# J-Link-OB.net
KiCad netlist of a schematic drawn in Altium Designer
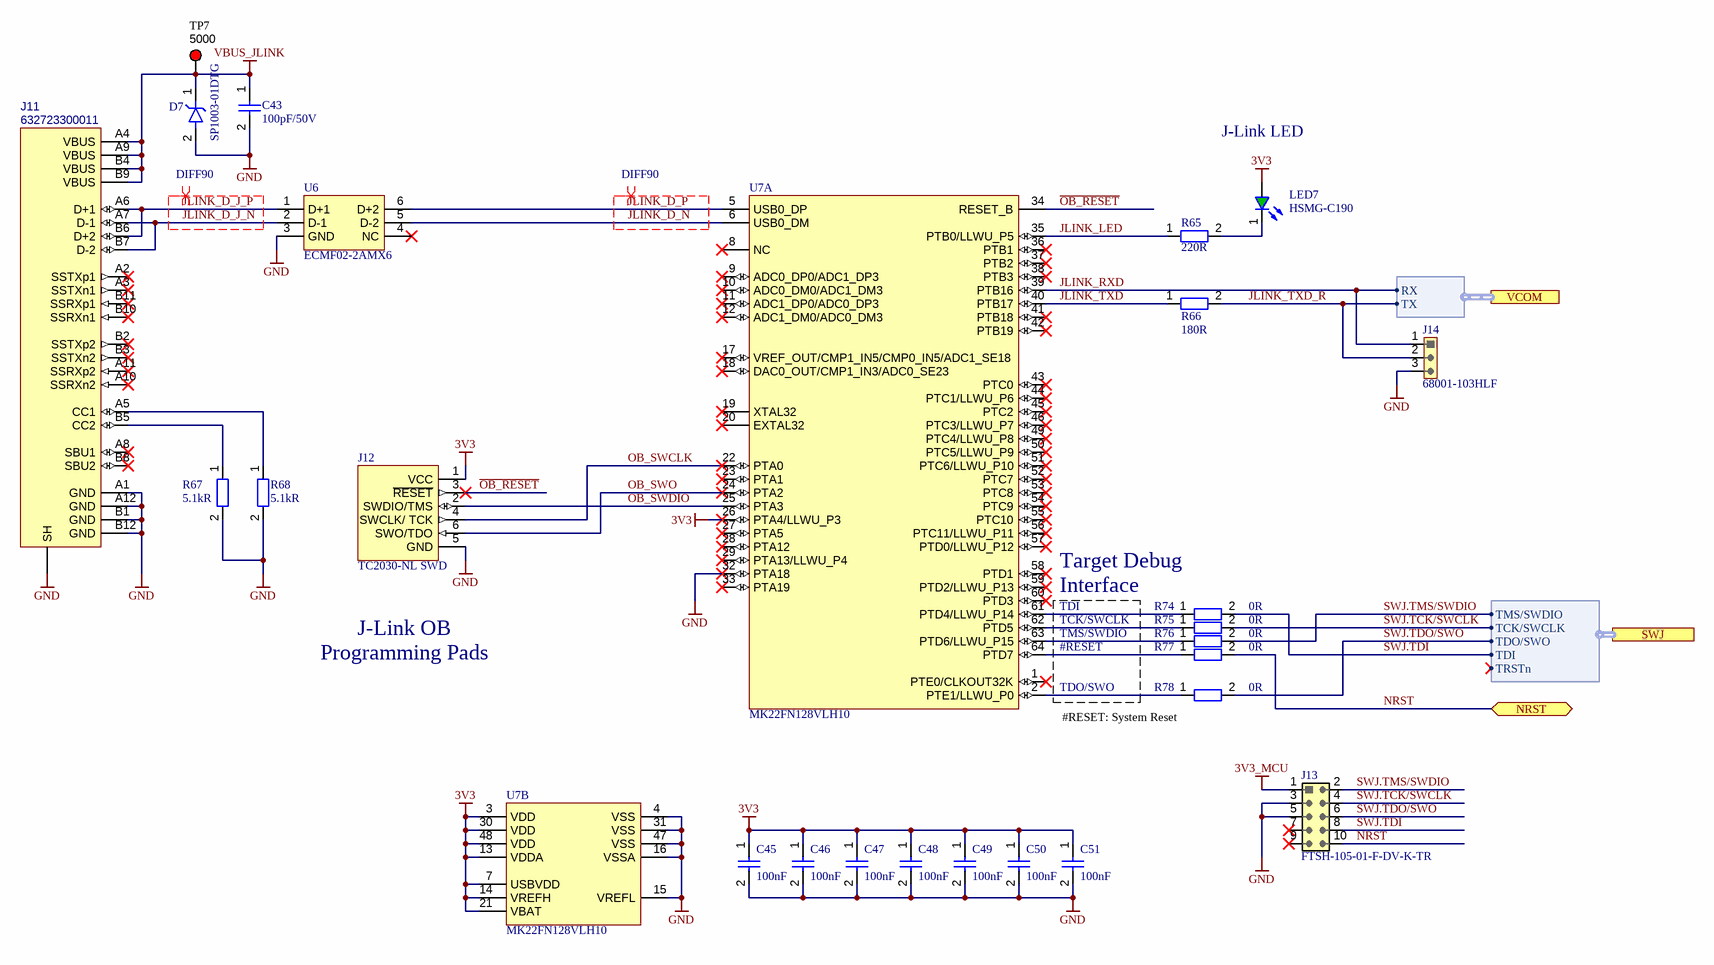
[diagram p0: J-Link-OB.SchDoc]

(export (version "E")
  (design (tool "Eeschema 10.0.6"))
  (components
    (comp (ref "C43")
      (value "100pF/50V")
      (footprint "CAPC1005X50N")
      (description "Cap MLCC, 100pF, 50V, C0G, 5%, 0402")
      (fields (field (name "TOLERANCE") "5%"))
      (libsource (lib "ZHAW on Altium 365") (part "CAP-NP-2"))
    )
    (comp (ref "C45")
      (value "100nF")
      (footprint "CAPC1005X50N")
      (description "Cap MLCC, 100nF, 16V, X7R, 5%,  0402")
      (fields (field (name "TOLERANCE") "5%") (field (name "Comment") "100nF/16V"))
      (libsource (lib "ZHAW on Altium 365") (part "CAP-NP-2"))
    )
    (comp (ref "C46")
      (value "100nF")
      (footprint "CAPC1005X50N")
      (description "Cap MLCC, 100nF, 16V, X7R, 5%,  0402")
      (fields (field (name "TOLERANCE") "5%") (field (name "Comment") "100nF/16V"))
      (libsource (lib "ZHAW on Altium 365") (part "CAP-NP-2"))
    )
    (comp (ref "C47")
      (value "100nF")
      (footprint "CAPC1005X50N")
      (description "Cap MLCC, 100nF, 16V, X7R, 5%,  0402")
      (fields (field (name "TOLERANCE") "5%") (field (name "Comment") "100nF/16V"))
      (libsource (lib "ZHAW on Altium 365") (part "CAP-NP-2"))
    )
    (comp (ref "C48")
      (value "100nF")
      (footprint "CAPC1005X50N")
      (description "Cap MLCC, 100nF, 16V, X7R, 5%,  0402")
      (fields (field (name "TOLERANCE") "5%") (field (name "Comment") "100nF/16V"))
      (libsource (lib "ZHAW on Altium 365") (part "CAP-NP-2"))
    )
    (comp (ref "C49")
      (value "100nF")
      (footprint "CAPC1005X50N")
      (description "Cap MLCC, 100nF, 16V, X7R, 5%,  0402")
      (fields (field (name "TOLERANCE") "5%") (field (name "Comment") "100nF/16V"))
      (libsource (lib "ZHAW on Altium 365") (part "CAP-NP-2"))
    )
    (comp (ref "C50")
      (value "100nF")
      (footprint "CAPC1005X50N")
      (description "Cap MLCC, 100nF, 16V, X7R, 5%,  0402")
      (fields (field (name "TOLERANCE") "5%") (field (name "Comment") "100nF/16V"))
      (libsource (lib "ZHAW on Altium 365") (part "CAP-NP-2"))
    )
    (comp (ref "C51")
      (value "100nF")
      (footprint "CAPC1005X50N")
      (description "Cap MLCC, 100nF, 16V, X7R, 5%,  0402")
      (fields (field (name "TOLERANCE") "5%") (field (name "Comment") "100nF/16V"))
      (libsource (lib "ZHAW on Altium 365") (part "CAP-NP-2"))
    )
    (comp (ref "D7")
      (value "SP1003-01DTG")
      (footprint "SOD14060X55N")
      (description "TVS Diode, unidirectional, 5V, 7A, SOD723")
      (libsource (lib "ZHAW on Altium 365") (part "D-TVS-KA-2"))
    )
    (comp (ref "J11")
      (value "632723300011")
      (footprint "WE_632723300011")
      (description "USB-C, 24 Pin, Pitch 500um, 20V, Horizontal, SMD/THT, L11.2B8.74H2.96")
      (fields (field (name "MANUFACTURER") "Wurth Elektronik"))
      (libsource (lib "ZHAW on Altium 365") (part "CN-USB-C-24"))
    )
    (comp (ref "J12")
      (value "TC2030-NL SWD")
      (footprint "TC2030-NL")
      (description "Land Pattern, Cortex Tag-Connect, 6 Pin, Pitch 1.27mm, no legs")
      (fields (field (name "MATING PART") "Cortex Tag-Connect Debugger"))
      (libsource (lib "ZHAW on Altium 365") (part "CN-TC2030-6"))
    )
    (comp (ref "J13")
      (value "FTSH-105-01-F-DV-K-TR")
      (footprint "FP-FTSH-105-01-F-DV-K-TR-MFG")
      (description "Box Header, FTSH-105, 2x5 Pin, Pitch 1.27mm, 3.4A, Vertical, SMD, L6.3B6.86H6")
      (fields (field (name "MANUFACTURER") "Samtec Inc."))
      (libsource (lib "ZHAW on Altium 365") (part "CN-BOXHDR-2x05-M-10"))
    )
    (comp (ref "J14")
      (value "68001-103HLF")
      (footprint "HD254_1x3_MV")
      (description "Header, 1x3 Pin, Pitch 2.54mm, Male, Vertical, THT")
      (fields (field (name "MANUFACTURER") "FCI"))
      (libsource (lib "ZHAW on Altium 365") (part "HDR-1x03-M-3"))
    )
    (comp (ref "LED7")
      (value "HSMG-C190")
      (footprint "LEDSC160X80X80-2Lgn")
      (description "LED, Green, 20mA, 2.2V, 0603")
      (libsource (lib "ZHAW on Altium 365") (part "LED-GN-KA-2"))
    )
    (comp (ref "R65")
      (value "220R")
      (footprint "RESC1608X45N")
      (description "Res, 220R, 1%, 0.1W, 0603")
      (fields (field (name "TOLERANCE") "1%") (field (name "POWER") "100mW"))
      (libsource (lib "ZHAW on Altium 365") (part "RES-2"))
    )
    (comp (ref "R66")
      (value "180R")
      (footprint "RESC1608X45N")
      (description "Res, 180R, 1%, 100mW, 0603")
      (fields (field (name "POWER") "100mW") (field (name "TOLERANCE") "1%"))
      (libsource (lib "ZHAW on Altium 365") (part "RES-2"))
    )
    (comp (ref "R67")
      (value "5.1kR")
      (footprint "RESC1005X35N")
      (description "Res, 5.1kR, 1%, 0.063W, 0402")
      (fields (field (name "TOLERANCE") "1%") (field (name "POWER") "63mW"))
      (libsource (lib "") (part "RES-2_1"))
    )
    (comp (ref "R68")
      (value "5.1kR")
      (footprint "RESC1005X35N")
      (description "Res, 5.1kR, 1%, 0.063W, 0402")
      (fields (field (name "TOLERANCE") "1%") (field (name "POWER") "63mW"))
      (libsource (lib "") (part "RES-2_1"))
    )
    (comp (ref "R74")
      (value "0R")
      (footprint "RESC1005X35N")
      (description "Res, 0R, 1%, 0.063W, 0402")
      (fields (field (name "POWER") "63mW") (field (name "TOLERANCE") "1%"))
      (libsource (lib "ZHAW on Altium 365") (part "RES-2"))
    )
    (comp (ref "R75")
      (value "0R")
      (footprint "RESC1005X35N")
      (description "Res, 0R, 1%, 0.063W, 0402")
      (fields (field (name "POWER") "63mW") (field (name "TOLERANCE") "1%"))
      (libsource (lib "ZHAW on Altium 365") (part "RES-2"))
    )
    (comp (ref "R76")
      (value "0R")
      (footprint "RESC1005X35N")
      (description "Res, 0R, 1%, 0.063W, 0402")
      (fields (field (name "POWER") "63mW") (field (name "TOLERANCE") "1%"))
      (libsource (lib "ZHAW on Altium 365") (part "RES-2"))
    )
    (comp (ref "R77")
      (value "0R")
      (footprint "RESC1005X35N")
      (description "Res, 0R, 1%, 0.063W, 0402")
      (fields (field (name "POWER") "63mW") (field (name "TOLERANCE") "1%"))
      (libsource (lib "ZHAW on Altium 365") (part "RES-2"))
    )
    (comp (ref "R78")
      (value "0R")
      (footprint "RESC1005X35N")
      (description "Res, 0R, 1%, 0.063W, 0402")
      (fields (field (name "POWER") "63mW") (field (name "TOLERANCE") "1%"))
      (libsource (lib "ZHAW on Altium 365") (part "RES-2"))
    )
    (comp (ref "TP7")
      (value "5000")
      (footprint "KSTN-5000")
      (description "Test Point, Red, D2.5H4.6, THT, closed ring D1.25")
      (libsource (lib "ZHAW on Altium 365") (part "TP-RD"))
    )
    (comp (ref "U6")
      (value "ECMF02-2AMX6")
      (footprint "QFN50P150X170X50-6N")
      (libsource (lib "ZHAW on Altium 365") (part "EMCMISC-ECMF02-2-6"))
    )
    (comp (ref "U7")
      (value "MK22FN128VLH10")
      (footprint "QFP50P1200X1200X160-64L")
      (description "Microcontroller, ARM Cortex-M4, 32MHz, Flash 128kB, RAM 24kB, QFN-64")
      (libsource (lib "ZHAW on Altium 365") (part "PROCESSOR-MK22FN128VLH10-64"))
    )
  )
  (nets
    (net (code "4") (name "/JLINK_D_J_N") (class "Default")
      (node (ref "J11") (pin "A7") (pinfunction "D-1_A7") (pintype "bidirectional"))
      (node (ref "J11") (pin "B7") (pinfunction "D-2_B7") (pintype "bidirectional"))
      (node (ref "U6") (pin "2") (pinfunction "D-1_2") (pintype "passive"))
    )
    (net (code "5") (name "/JLINK_D_J_P") (class "Default")
      (node (ref "J11") (pin "A6") (pinfunction "D+1_A6") (pintype "bidirectional"))
      (node (ref "J11") (pin "B6") (pinfunction "D+2_B6") (pintype "bidirectional"))
      (node (ref "U6") (pin "1") (pinfunction "D+1_1") (pintype "passive"))
    )
    (net (code "6") (name "/JLINK_D_N") (class "Default")
      (node (ref "U6") (pin "5") (pinfunction "D-2_5") (pintype "passive"))
      (node (ref "U7") (pin "6") (pinfunction "USB0_DM_6") (pintype "passive"))
    )
    (net (code "7") (name "/JLINK_D_P") (class "Default")
      (node (ref "U6") (pin "6") (pinfunction "D+2_6") (pintype "passive"))
      (node (ref "U7") (pin "5") (pinfunction "USB0_DP_5") (pintype "passive"))
    )
    (net (code "8") (name "/JLINK_LED") (class "Default")
      (node (ref "R65") (pin "1") (pinfunction "1_1") (pintype "passive"))
      (node (ref "U7") (pin "35") (pinfunction "PTB0/LLWU_P5_35") (pintype "bidirectional"))
    )
    (net (code "9") (name "/JLINK_RXD") (class "Default")
      (node (ref "J14") (pin "1") (pinfunction "1_1") (pintype "passive"))
      (node (ref "U7") (pin "39") (pinfunction "PTB16_39") (pintype "bidirectional"))
    )
    (net (code "10") (name "/JLINK_TXD") (class "Default")
      (node (ref "R66") (pin "1") (pinfunction "1_1") (pintype "passive"))
      (node (ref "U7") (pin "40") (pinfunction "PTB17_40") (pintype "bidirectional"))
    )
    (net (code "11") (name "/JLINK_TXD_R") (class "Default")
      (node (ref "J14") (pin "2") (pinfunction "2_2") (pintype "passive"))
      (node (ref "R66") (pin "2") (pinfunction "2_2") (pintype "passive"))
    )
    (net (code "12") (name "/NRST") (class "Default")
      (node (ref "J13") (pin "10") (pinfunction "10_10") (pintype "passive"))
      (node (ref "R77") (pin "2") (pinfunction "2_2") (pintype "passive"))
    )
    (net (code "13") (name "/OB_SWCLK") (class "Default")
      (node (ref "J12") (pin "4") (pinfunction "SWCLK/_TCK_4") (pintype "output"))
      (node (ref "U7") (pin "22") (pinfunction "PTA0_22") (pintype "bidirectional"))
    )
    (net (code "14") (name "/OB_SWDIO") (class "Default")
      (node (ref "J12") (pin "2") (pinfunction "SWDIO/TMS_2") (pintype "bidirectional"))
      (node (ref "U7") (pin "25") (pinfunction "PTA3_25") (pintype "bidirectional"))
    )
    (net (code "15") (name "/OB_SWO") (class "Default")
      (node (ref "J12") (pin "6") (pinfunction "SWO/TDO_6") (pintype "input"))
      (node (ref "U7") (pin "24") (pinfunction "PTA2_24") (pintype "bidirectional"))
    )
    (net (code "16") (name "/SWJ.TCK{slash}SWCLK") (class "Default")
      (node (ref "J13") (pin "4") (pinfunction "4_4") (pintype "passive"))
      (node (ref "R75") (pin "2") (pinfunction "2_2") (pintype "passive"))
    )
    (net (code "17") (name "/SWJ.TDI") (class "Default")
      (node (ref "J13") (pin "8") (pinfunction "8_8") (pintype "passive"))
      (node (ref "R74") (pin "2") (pinfunction "2_2") (pintype "passive"))
    )
    (net (code "18") (name "/SWJ.TDO{slash}SWO") (class "Default")
      (node (ref "J13") (pin "6") (pinfunction "6_6") (pintype "passive"))
      (node (ref "R78") (pin "2") (pinfunction "2_2") (pintype "passive"))
    )
    (net (code "19") (name "/SWJ.TMS{slash}SWDIO") (class "Default")
      (node (ref "J13") (pin "2") (pinfunction "2_2") (pintype "passive"))
      (node (ref "R76") (pin "2") (pinfunction "2_2") (pintype "passive"))
    )
    (net (code "22") (name "/~{OB_RESET}") (class "Default")
      (node (ref "J12") (pin "3") (pinfunction "~{RESET}_3") (pintype "output"))
      (node (ref "U7") (pin "34") (pinfunction "RESET_B_34") (pintype "passive"))
    )
    (net (code "23") (name "3V3") (class "Default")
      (node (ref "C45") (pin "1") (pinfunction "1_1") (pintype "passive"))
      (node (ref "C46") (pin "1") (pinfunction "1_1") (pintype "passive"))
      (node (ref "C47") (pin "1") (pinfunction "1_1") (pintype "passive"))
      (node (ref "C48") (pin "1") (pinfunction "1_1") (pintype "passive"))
      (node (ref "C49") (pin "1") (pinfunction "1_1") (pintype "passive"))
      (node (ref "C50") (pin "1") (pinfunction "1_1") (pintype "passive"))
      (node (ref "C51") (pin "1") (pinfunction "1_1") (pintype "passive"))
      (node (ref "J12") (pin "1") (pinfunction "VCC_1") (pintype "passive"))
      (node (ref "LED7") (pin "2") (pinfunction "A_2") (pintype "passive"))
      (node (ref "U7") (pin "13") (pinfunction "VDDA_13") (pintype "power_in"))
      (node (ref "U7") (pin "14") (pinfunction "VREFH_14") (pintype "power_in"))
      (node (ref "U7") (pin "21") (pinfunction "VBAT_21") (pintype "power_in"))
      (node (ref "U7") (pin "26") (pinfunction "PTA4/LLWU_P3_26") (pintype "bidirectional"))
      (node (ref "U7") (pin "3") (pinfunction "VDD_3") (pintype "power_in"))
      (node (ref "U7") (pin "30") (pinfunction "VDD_30") (pintype "power_in"))
      (node (ref "U7") (pin "48") (pinfunction "VDD_48") (pintype "power_in"))
      (node (ref "U7") (pin "7") (pinfunction "USBVDD_7") (pintype "power_in"))
    )
    (net (code "24") (name "3V3_MCU") (class "Default")
      (node (ref "J13") (pin "1") (pinfunction "1_1") (pintype "passive"))
    )
    (net (code "25") (name "GND") (class "Default")
      (node (ref "C43") (pin "2") (pinfunction "2_2") (pintype "passive"))
      (node (ref "C45") (pin "2") (pinfunction "2_2") (pintype "passive"))
      (node (ref "C46") (pin "2") (pinfunction "2_2") (pintype "passive"))
      (node (ref "C47") (pin "2") (pinfunction "2_2") (pintype "passive"))
      (node (ref "C48") (pin "2") (pinfunction "2_2") (pintype "passive"))
      (node (ref "C49") (pin "2") (pinfunction "2_2") (pintype "passive"))
      (node (ref "C50") (pin "2") (pinfunction "2_2") (pintype "passive"))
      (node (ref "C51") (pin "2") (pinfunction "2_2") (pintype "passive"))
      (node (ref "D7") (pin "2") (pinfunction "A_2") (pintype "passive"))
      (node (ref "J11") (pin "A1") (pinfunction "GND_A1") (pintype "power_in"))
      (node (ref "J11") (pin "A12") (pinfunction "GND_A12") (pintype "power_in"))
      (node (ref "J11") (pin "B1") (pinfunction "GND_B1") (pintype "power_in"))
      (node (ref "J11") (pin "B12") (pinfunction "GND_B12") (pintype "power_in"))
      (node (ref "J11") (pin "SH") (pinfunction "SH_SH") (pintype "passive"))
      (node (ref "J12") (pin "5") (pinfunction "GND_5") (pintype "passive"))
      (node (ref "J13") (pin "3") (pinfunction "3_3") (pintype "passive"))
      (node (ref "J13") (pin "5") (pinfunction "5_5") (pintype "passive"))
      (node (ref "J14") (pin "3") (pinfunction "3_3") (pintype "passive"))
      (node (ref "R67") (pin "2") (pinfunction "2_2") (pintype "passive"))
      (node (ref "R68") (pin "2") (pinfunction "2_2") (pintype "passive"))
      (node (ref "U6") (pin "3") (pinfunction "GND_3") (pintype "power_in"))
      (node (ref "U7") (pin "15") (pinfunction "VREFL_15") (pintype "power_in"))
      (node (ref "U7") (pin "16") (pinfunction "VSSA_16") (pintype "power_in"))
      (node (ref "U7") (pin "31") (pinfunction "VSS_31") (pintype "power_in"))
      (node (ref "U7") (pin "32") (pinfunction "PTA18_32") (pintype "bidirectional"))
      (node (ref "U7") (pin "4") (pinfunction "VSS_4") (pintype "power_in"))
      (node (ref "U7") (pin "47") (pinfunction "VSS_47") (pintype "power_in"))
    )
    (net (code "26") (name "Net-(J11-CC1)") (class "Default")
      (node (ref "J11") (pin "A5") (pinfunction "CC1_A5") (pintype "bidirectional"))
      (node (ref "R68") (pin "1") (pinfunction "1_1") (pintype "passive"))
    )
    (net (code "27") (name "Net-(J11-CC2)") (class "Default")
      (node (ref "J11") (pin "B5") (pinfunction "CC2_B5") (pintype "bidirectional"))
      (node (ref "R67") (pin "1") (pinfunction "1_1") (pintype "passive"))
    )
    (net (code "28") (name "Net-(LED7-K)") (class "Default")
      (node (ref "LED7") (pin "1") (pinfunction "K_1") (pintype "passive"))
      (node (ref "R65") (pin "2") (pinfunction "2_2") (pintype "passive"))
    )
    (net (code "29") (name "Net-(U7A-PTD4{slash}LLWU_P14)") (class "Default")
      (node (ref "R74") (pin "1") (pinfunction "1_1") (pintype "passive"))
      (node (ref "U7") (pin "61") (pinfunction "PTD4/LLWU_P14_61") (pintype "bidirectional"))
    )
    (net (code "30") (name "Net-(U7A-PTD5)") (class "Default")
      (node (ref "R75") (pin "1") (pinfunction "1_1") (pintype "passive"))
      (node (ref "U7") (pin "62") (pinfunction "PTD5_62") (pintype "bidirectional"))
    )
    (net (code "31") (name "Net-(U7A-PTD6{slash}LLWU_P15)") (class "Default")
      (node (ref "R76") (pin "1") (pinfunction "1_1") (pintype "passive"))
      (node (ref "U7") (pin "63") (pinfunction "PTD6/LLWU_P15_63") (pintype "bidirectional"))
    )
    (net (code "32") (name "Net-(U7A-PTD7)") (class "Default")
      (node (ref "R77") (pin "1") (pinfunction "1_1") (pintype "passive"))
      (node (ref "U7") (pin "64") (pinfunction "PTD7_64") (pintype "bidirectional"))
    )
    (net (code "33") (name "Net-(U7A-PTE1{slash}LLWU_P0)") (class "Default")
      (node (ref "R78") (pin "1") (pinfunction "1_1") (pintype "passive"))
      (node (ref "U7") (pin "2") (pinfunction "PTE1/LLWU_P0_2") (pintype "bidirectional"))
    )
    (net (code "34") (name "VBUS_JLINK") (class "Default")
      (node (ref "C43") (pin "1") (pinfunction "1_1") (pintype "passive"))
      (node (ref "D7") (pin "1") (pinfunction "A_1") (pintype "passive"))
      (node (ref "J11") (pin "A4") (pinfunction "VBUS_A4") (pintype "power_in"))
      (node (ref "J11") (pin "A9") (pinfunction "VBUS_A9") (pintype "power_in"))
      (node (ref "J11") (pin "B4") (pinfunction "VBUS_B4") (pintype "power_in"))
      (node (ref "J11") (pin "B9") (pinfunction "VBUS_B9") (pintype "power_in"))
      (node (ref "TP7") (pin "1") (pinfunction "1_1") (pintype "passive"))
    )
    (net (code "35") (name "unconnected-(J11-SBU1-PadA8)") (class "Default")
      (node (ref "J11") (pin "A8") (pinfunction "SBU1_A8") (pintype "bidirectional+no_connect"))
    )
    (net (code "36") (name "unconnected-(J11-SBU2-PadB8)") (class "Default")
      (node (ref "J11") (pin "B8") (pinfunction "SBU2_B8") (pintype "bidirectional+no_connect"))
    )
    (net (code "37") (name "unconnected-(J11-SSRXn1-PadB10)") (class "Default")
      (node (ref "J11") (pin "B10") (pinfunction "SSRXn1_B10") (pintype "input+no_connect"))
    )
    (net (code "38") (name "unconnected-(J11-SSRXn2-PadA10)") (class "Default")
      (node (ref "J11") (pin "A10") (pinfunction "SSRXn2_A10") (pintype "input+no_connect"))
    )
    (net (code "39") (name "unconnected-(J11-SSRXp1-PadB11)") (class "Default")
      (node (ref "J11") (pin "B11") (pinfunction "SSRXp1_B11") (pintype "input+no_connect"))
    )
    (net (code "40") (name "unconnected-(J11-SSRXp2-PadA11)") (class "Default")
      (node (ref "J11") (pin "A11") (pinfunction "SSRXp2_A11") (pintype "input+no_connect"))
    )
    (net (code "41") (name "unconnected-(J11-SSTXn1-PadA3)") (class "Default")
      (node (ref "J11") (pin "A3") (pinfunction "SSTXn1_A3") (pintype "output+no_connect"))
    )
    (net (code "42") (name "unconnected-(J11-SSTXn2-PadB3)") (class "Default")
      (node (ref "J11") (pin "B3") (pinfunction "SSTXn2_B3") (pintype "output+no_connect"))
    )
    (net (code "43") (name "unconnected-(J11-SSTXp1-PadA2)") (class "Default")
      (node (ref "J11") (pin "A2") (pinfunction "SSTXp1_A2") (pintype "output+no_connect"))
    )
    (net (code "44") (name "unconnected-(J11-SSTXp2-PadB2)") (class "Default")
      (node (ref "J11") (pin "B2") (pinfunction "SSTXp2_B2") (pintype "output+no_connect"))
    )
    (net (code "45") (name "unconnected-(J13-Pad7)") (class "Default")
      (node (ref "J13") (pin "7") (pinfunction "7_7") (pintype "passive+no_connect"))
    )
    (net (code "46") (name "unconnected-(J13-Pad9)") (class "Default")
      (node (ref "J13") (pin "9") (pinfunction "9_9") (pintype "passive+no_connect"))
    )
    (net (code "47") (name "unconnected-(U6-NC-Pad4)") (class "Default")
      (node (ref "U6") (pin "4") (pinfunction "NC_4") (pintype "passive+no_connect"))
    )
    (net (code "48") (name "unconnected-(U7A-ADC0_DM0{slash}ADC1_DM3-Pad10)") (class "Default")
      (node (ref "U7") (pin "10") (pinfunction "ADC0_DM0/ADC1_DM3_10") (pintype "bidirectional+no_connect"))
    )
    (net (code "49") (name "unconnected-(U7A-ADC0_DP0{slash}ADC1_DP3-Pad9)") (class "Default")
      (node (ref "U7") (pin "9") (pinfunction "ADC0_DP0/ADC1_DP3_9") (pintype "bidirectional+no_connect"))
    )
    (net (code "50") (name "unconnected-(U7A-ADC1_DM0{slash}ADC0_DM3-Pad12)") (class "Default")
      (node (ref "U7") (pin "12") (pinfunction "ADC1_DM0/ADC0_DM3_12") (pintype "bidirectional+no_connect"))
    )
    (net (code "51") (name "unconnected-(U7A-ADC1_DP0{slash}ADC0_DP3-Pad11)") (class "Default")
      (node (ref "U7") (pin "11") (pinfunction "ADC1_DP0/ADC0_DP3_11") (pintype "bidirectional+no_connect"))
    )
    (net (code "52") (name "unconnected-(U7A-DAC0_OUT{slash}CMP1_IN3{slash}ADC0_SE23-Pad18)") (class "Default")
      (node (ref "U7") (pin "18") (pinfunction "DAC0_OUT/CMP1_IN3/ADC0_SE23_18") (pintype "bidirectional+no_connect"))
    )
    (net (code "53") (name "unconnected-(U7A-EXTAL32-Pad20)") (class "Default")
      (node (ref "U7") (pin "20") (pinfunction "EXTAL32_20") (pintype "passive+no_connect"))
    )
    (net (code "54") (name "unconnected-(U7A-NC-Pad8)") (class "Default")
      (node (ref "U7") (pin "8") (pinfunction "NC_8") (pintype "passive+no_connect"))
    )
    (net (code "55") (name "unconnected-(U7A-PTA1-Pad23)") (class "Default")
      (node (ref "U7") (pin "23") (pinfunction "PTA1_23") (pintype "bidirectional+no_connect"))
    )
    (net (code "56") (name "unconnected-(U7A-PTA5-Pad27)") (class "Default")
      (node (ref "U7") (pin "27") (pinfunction "PTA5_27") (pintype "bidirectional+no_connect"))
    )
    (net (code "57") (name "unconnected-(U7A-PTA12-Pad28)") (class "Default")
      (node (ref "U7") (pin "28") (pinfunction "PTA12_28") (pintype "bidirectional+no_connect"))
    )
    (net (code "58") (name "unconnected-(U7A-PTA13{slash}LLWU_P4-Pad29)") (class "Default")
      (node (ref "U7") (pin "29") (pinfunction "PTA13/LLWU_P4_29") (pintype "bidirectional+no_connect"))
    )
    (net (code "59") (name "unconnected-(U7A-PTA19-Pad33)") (class "Default")
      (node (ref "U7") (pin "33") (pinfunction "PTA19_33") (pintype "bidirectional+no_connect"))
    )
    (net (code "60") (name "unconnected-(U7A-PTB1-Pad36)") (class "Default")
      (node (ref "U7") (pin "36") (pinfunction "PTB1_36") (pintype "bidirectional+no_connect"))
    )
    (net (code "61") (name "unconnected-(U7A-PTB2-Pad37)") (class "Default")
      (node (ref "U7") (pin "37") (pinfunction "PTB2_37") (pintype "bidirectional+no_connect"))
    )
    (net (code "62") (name "unconnected-(U7A-PTB3-Pad38)") (class "Default")
      (node (ref "U7") (pin "38") (pinfunction "PTB3_38") (pintype "bidirectional+no_connect"))
    )
    (net (code "63") (name "unconnected-(U7A-PTB18-Pad41)") (class "Default")
      (node (ref "U7") (pin "41") (pinfunction "PTB18_41") (pintype "bidirectional+no_connect"))
    )
    (net (code "64") (name "unconnected-(U7A-PTB19-Pad42)") (class "Default")
      (node (ref "U7") (pin "42") (pinfunction "PTB19_42") (pintype "bidirectional+no_connect"))
    )
    (net (code "65") (name "unconnected-(U7A-PTC0-Pad43)") (class "Default")
      (node (ref "U7") (pin "43") (pinfunction "PTC0_43") (pintype "bidirectional+no_connect"))
    )
    (net (code "66") (name "unconnected-(U7A-PTC1{slash}LLWU_P6-Pad44)") (class "Default")
      (node (ref "U7") (pin "44") (pinfunction "PTC1/LLWU_P6_44") (pintype "bidirectional+no_connect"))
    )
    (net (code "67") (name "unconnected-(U7A-PTC2-Pad45)") (class "Default")
      (node (ref "U7") (pin "45") (pinfunction "PTC2_45") (pintype "bidirectional+no_connect"))
    )
    (net (code "68") (name "unconnected-(U7A-PTC3{slash}LLWU_P7-Pad46)") (class "Default")
      (node (ref "U7") (pin "46") (pinfunction "PTC3/LLWU_P7_46") (pintype "bidirectional+no_connect"))
    )
    (net (code "69") (name "unconnected-(U7A-PTC4{slash}LLWU_P8-Pad49)") (class "Default")
      (node (ref "U7") (pin "49") (pinfunction "PTC4/LLWU_P8_49") (pintype "bidirectional+no_connect"))
    )
    (net (code "70") (name "unconnected-(U7A-PTC5{slash}LLWU_P9-Pad50)") (class "Default")
      (node (ref "U7") (pin "50") (pinfunction "PTC5/LLWU_P9_50") (pintype "bidirectional+no_connect"))
    )
    (net (code "71") (name "unconnected-(U7A-PTC6{slash}LLWU_P10-Pad51)") (class "Default")
      (node (ref "U7") (pin "51") (pinfunction "PTC6/LLWU_P10_51") (pintype "bidirectional+no_connect"))
    )
    (net (code "72") (name "unconnected-(U7A-PTC7-Pad52)") (class "Default")
      (node (ref "U7") (pin "52") (pinfunction "PTC7_52") (pintype "bidirectional+no_connect"))
    )
    (net (code "73") (name "unconnected-(U7A-PTC8-Pad53)") (class "Default")
      (node (ref "U7") (pin "53") (pinfunction "PTC8_53") (pintype "bidirectional+no_connect"))
    )
    (net (code "74") (name "unconnected-(U7A-PTC9-Pad54)") (class "Default")
      (node (ref "U7") (pin "54") (pinfunction "PTC9_54") (pintype "bidirectional+no_connect"))
    )
    (net (code "75") (name "unconnected-(U7A-PTC10-Pad55)") (class "Default")
      (node (ref "U7") (pin "55") (pinfunction "PTC10_55") (pintype "bidirectional+no_connect"))
    )
    (net (code "76") (name "unconnected-(U7A-PTC11{slash}LLWU_P11-Pad56)") (class "Default")
      (node (ref "U7") (pin "56") (pinfunction "PTC11/LLWU_P11_56") (pintype "bidirectional+no_connect"))
    )
    (net (code "77") (name "unconnected-(U7A-PTD0{slash}LLWU_P12-Pad57)") (class "Default")
      (node (ref "U7") (pin "57") (pinfunction "PTD0/LLWU_P12_57") (pintype "bidirectional+no_connect"))
    )
    (net (code "78") (name "unconnected-(U7A-PTD1-Pad58)") (class "Default")
      (node (ref "U7") (pin "58") (pinfunction "PTD1_58") (pintype "bidirectional+no_connect"))
    )
    (net (code "79") (name "unconnected-(U7A-PTD2{slash}LLWU_P13-Pad59)") (class "Default")
      (node (ref "U7") (pin "59") (pinfunction "PTD2/LLWU_P13_59") (pintype "bidirectional+no_connect"))
    )
    (net (code "80") (name "unconnected-(U7A-PTD3-Pad60)") (class "Default")
      (node (ref "U7") (pin "60") (pinfunction "PTD3_60") (pintype "bidirectional+no_connect"))
    )
    (net (code "81") (name "unconnected-(U7A-PTE0{slash}CLKOUT32K-Pad1)") (class "Default")
      (node (ref "U7") (pin "1") (pinfunction "PTE0/CLKOUT32K_1") (pintype "bidirectional+no_connect"))
    )
    (net (code "82") (name "unconnected-(U7A-VREF_OUT{slash}CMP1_IN5{slash}CMP0_IN5{slash}ADC1_SE18-Pad17)") (class "Default")
      (node (ref "U7") (pin "17") (pinfunction "VREF_OUT/CMP1_IN5/CMP0_IN5/ADC1_SE18_17") (pintype "bidirectional+no_connect"))
    )
    (net (code "83") (name "unconnected-(U7A-XTAL32-Pad19)") (class "Default")
      (node (ref "U7") (pin "19") (pinfunction "XTAL32_19") (pintype "passive+no_connect"))
    )
  )
)
